# fabisp.net
KiCad netlist of a schematic drawn in EAGLE
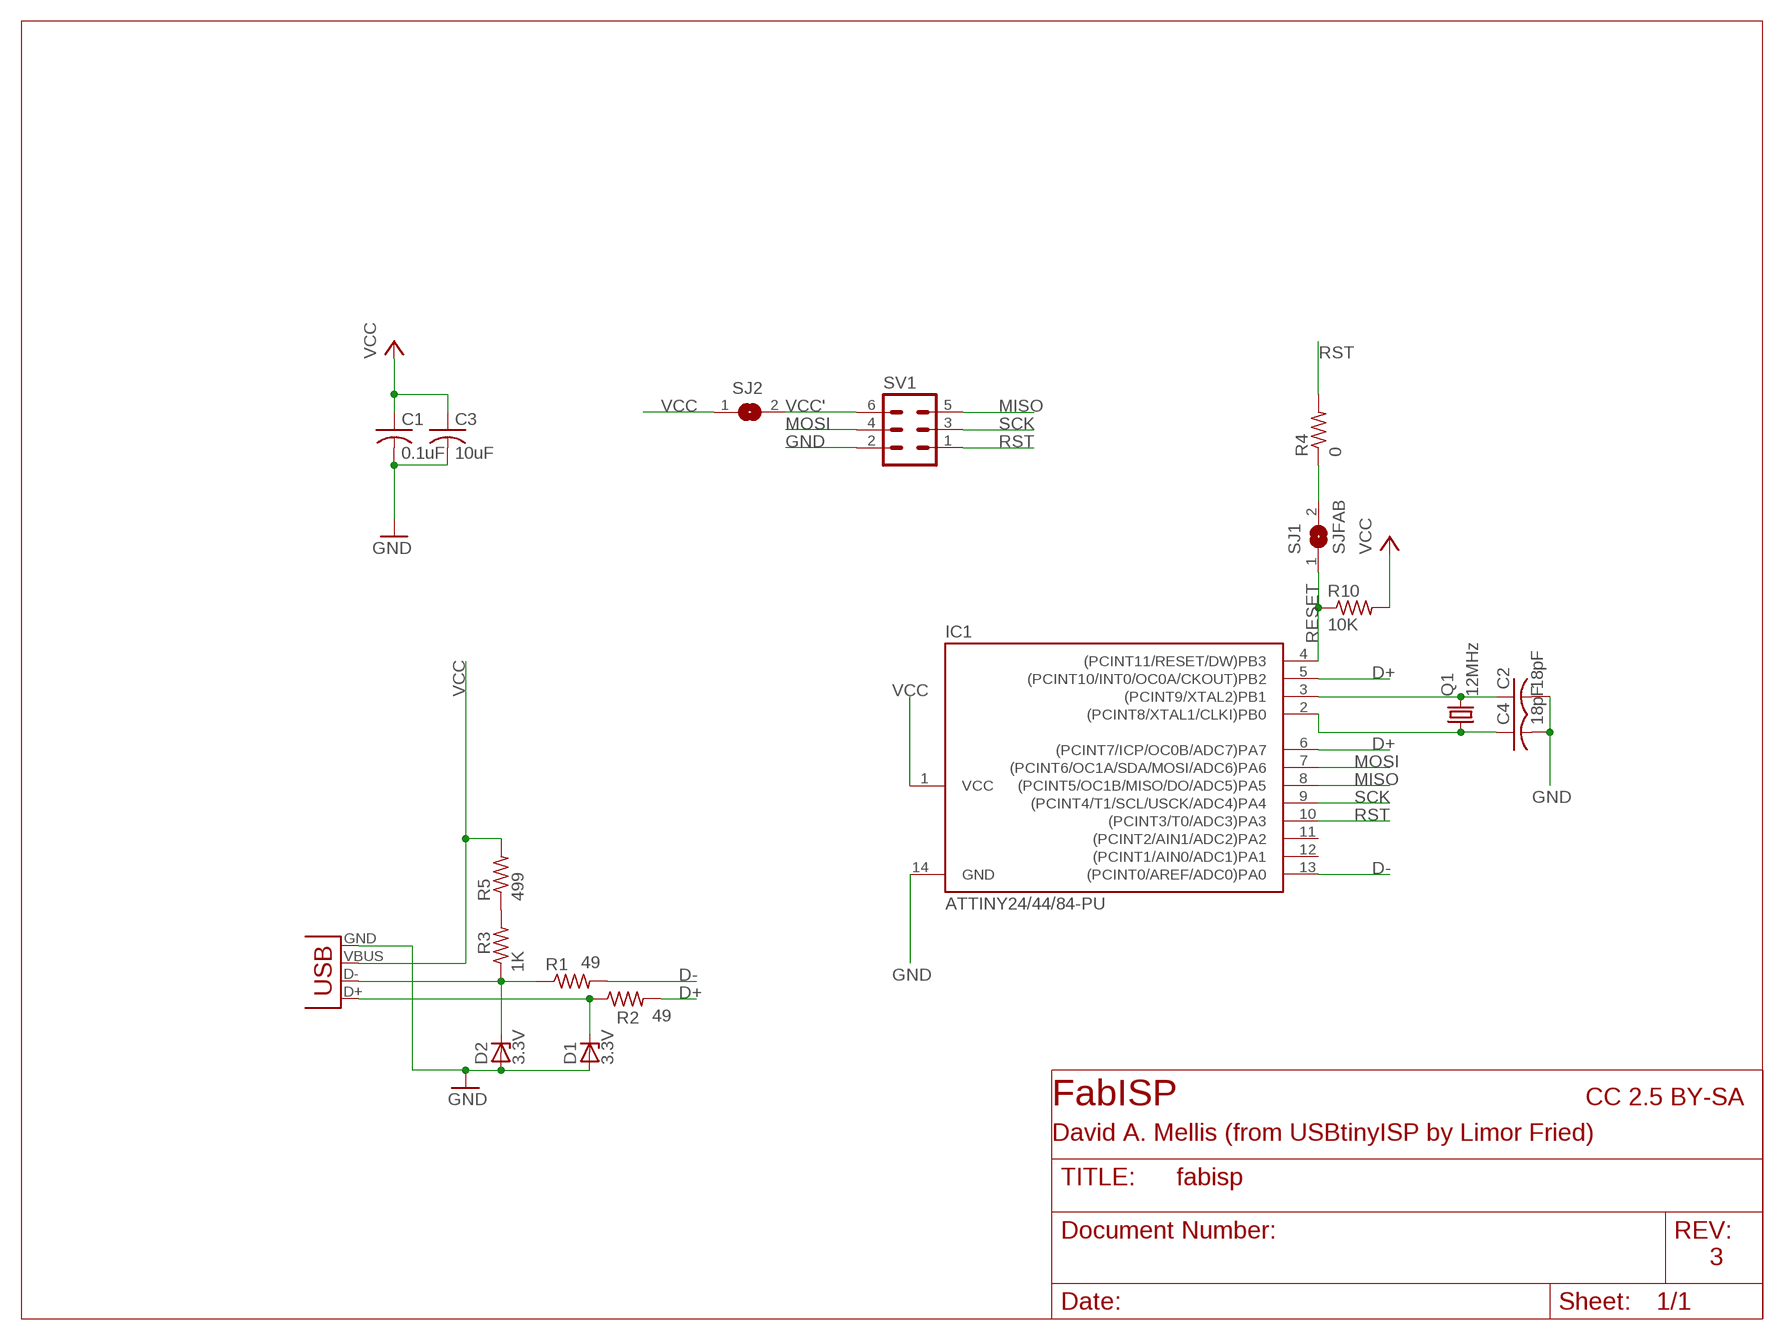
[diagram p0: schematic, sheet 1]

(export (version "E")
  (design (tool "Eeschema 10.0.6"))
  (components
    (comp (ref "C1")
      (value "0.1uF")
      (footprint "eagle-import:C025-024X044")
      (libsource (lib "eagle-import") (part "rcl-ez_C-US025-024X044"))
    )
    (comp (ref "C2")
      (value "18pF")
      (footprint "eagle-import:C025-024X044")
      (libsource (lib "eagle-import") (part "C-US025-024X044"))
    )
    (comp (ref "C3")
      (value "10uF")
      (footprint "eagle-import:C025-024X044")
      (libsource (lib "eagle-import") (part "C-US025-024X044"))
    )
    (comp (ref "C4")
      (value "18pF")
      (footprint "eagle-import:C025-024X044")
      (libsource (lib "eagle-import") (part "C-US025-024X044"))
    )
    (comp (ref "D1")
      (value "3.3V")
      (footprint "eagle-import:DO41Z10")
      (libsource (lib "eagle-import") (part "ZENER_DIODEDO41Z10"))
    )
    (comp (ref "D2")
      (value "3.3V")
      (footprint "eagle-import:DO41Z10")
      (libsource (lib "eagle-import") (part "ZENER_DIODEDO41Z10"))
    )
    (comp (ref "IC1")
      (value "ATTINY24/44/84-PU")
      (footprint "eagle-import:DIL14")
      (libsource (lib "eagle-import") (part "ATTINY24/44/84-PU"))
    )
    (comp (ref "Q1")
      (value "12MHz")
      (footprint "eagle-import:HC49U-V")
      (libsource (lib "eagle-import") (part "CRYSTALHC49U-V"))
    )
    (comp (ref "R1")
      (value "49")
      (footprint "eagle-import:0204_7")
      (libsource (lib "eagle-import") (part "rcl-ez_R-US_0204/7"))
    )
    (comp (ref "R2")
      (value "49")
      (footprint "eagle-import:0204_7")
      (libsource (lib "eagle-import") (part "rcl-ez_R-US_0204/7"))
    )
    (comp (ref "R3")
      (value "1K")
      (footprint "eagle-import:0204_7")
      (libsource (lib "eagle-import") (part "rcl-ez_R-US_0204/7"))
    )
    (comp (ref "R4")
      (value "0")
      (footprint "eagle-import:0204_7")
      (libsource (lib "eagle-import") (part "R-US_0204/7"))
    )
    (comp (ref "R5")
      (value "499")
      (footprint "eagle-import:0204_7")
      (libsource (lib "eagle-import") (part "R-US_0204/7"))
    )
    (comp (ref "R10")
      (value "10K")
      (footprint "eagle-import:0204_7")
      (libsource (lib "eagle-import") (part "rcl-ez_R-US_0204/7"))
    )
    (comp (ref "SJ1")
      (value "SJFAB")
      (footprint "eagle-import:SJFAB")
      (libsource (lib "eagle-import") (part "SJFAB"))
    )
    (comp (ref "SJ2")
      (value "SJFAB")
      (footprint "eagle-import:SJFAB")
      (libsource (lib "eagle-import") (part "SJFAB"))
    )
    (comp (ref "SV1")
      (value "MA03-2")
      (footprint "eagle-import:MA03-2")
      (libsource (lib "eagle-import") (part "MA03-2"))
    )
    (comp (ref "X1")
      (value "USB_MINIB")
      (footprint "eagle-import:USB_MINIB")
      (libsource (lib "eagle-import") (part "USB_MINIB"))
    )
  )
  (nets
    (net (code "1") (name "/D+") (class "Default")
      (node (ref "IC1") (pin "5") (pinfunction "(PCINT10/INT0/OC0A/CKOUT)PB2_5") (pintype "bidirectional"))
      (node (ref "IC1") (pin "6") (pinfunction "(PCINT7/ICP/OC0B/ADC7)PA7_6") (pintype "bidirectional"))
      (node (ref "R2") (pin "2") (pinfunction "2_2") (pintype "passive"))
    )
    (net (code "2") (name "/D-") (class "Default")
      (node (ref "IC1") (pin "13") (pinfunction "(PCINT0/AREF/ADC0)PA0_13") (pintype "bidirectional"))
      (node (ref "R1") (pin "2") (pinfunction "2_2") (pintype "passive"))
    )
    (net (code "3") (name "/MISO") (class "Default")
      (node (ref "IC1") (pin "8") (pinfunction "(PCINT5/OC1B/MISO/DO/ADC5)PA5_8") (pintype "bidirectional"))
      (node (ref "SV1") (pin "5") (pinfunction "5_5") (pintype "passive"))
    )
    (net (code "4") (name "/MOSI") (class "Default")
      (node (ref "IC1") (pin "7") (pinfunction "(PCINT6/OC1A/SDA/MOSI/ADC6)PA6_7") (pintype "bidirectional"))
      (node (ref "SV1") (pin "4") (pinfunction "4_4") (pintype "passive"))
    )
    (net (code "5") (name "/RESET") (class "Default")
      (node (ref "IC1") (pin "4") (pinfunction "(PCINT11/RESET/DW)PB3_4") (pintype "bidirectional"))
      (node (ref "R10") (pin "1") (pinfunction "1_1") (pintype "passive"))
      (node (ref "SJ1") (pin "1") (pinfunction "1_1") (pintype "passive"))
    )
    (net (code "6") (name "/RST") (class "Default")
      (node (ref "IC1") (pin "10") (pinfunction "(PCINT3/T0/ADC3)PA3_10") (pintype "bidirectional"))
      (node (ref "R4") (pin "2") (pinfunction "2_2") (pintype "passive"))
      (node (ref "SV1") (pin "1") (pinfunction "1_1") (pintype "passive"))
    )
    (net (code "7") (name "/SCK") (class "Default")
      (node (ref "IC1") (pin "9") (pinfunction "(PCINT4/T1/SCL/USCK/ADC4)PA4_9") (pintype "bidirectional"))
      (node (ref "SV1") (pin "3") (pinfunction "3_3") (pintype "passive"))
    )
    (net (code "8") (name "/VCC'") (class "Default")
      (node (ref "SJ2") (pin "2") (pinfunction "2_2") (pintype "passive"))
      (node (ref "SV1") (pin "6") (pinfunction "6_6") (pintype "passive"))
    )
    (net (code "9") (name "GND") (class "Default")
      (node (ref "C1") (pin "2") (pinfunction "2_2") (pintype "passive"))
      (node (ref "C2") (pin "2") (pinfunction "2_2") (pintype "passive"))
      (node (ref "C3") (pin "2") (pinfunction "2_2") (pintype "passive"))
      (node (ref "C4") (pin "2") (pinfunction "2_2") (pintype "passive"))
      (node (ref "D1") (pin "A") (pinfunction "ANODE_A") (pintype "passive"))
      (node (ref "D2") (pin "A") (pinfunction "ANODE_A") (pintype "passive"))
      (node (ref "IC1") (pin "14") (pinfunction "GND_14") (pintype "power_in"))
      (node (ref "SV1") (pin "2") (pinfunction "2_2") (pintype "passive"))
      (node (ref "X1") (pin "GND") (pinfunction "GND_GND") (pintype "bidirectional"))
    )
    (net (code "10") (name "Net-(D1-CATHODE)") (class "Default")
      (node (ref "D1") (pin "C") (pinfunction "CATHODE_C") (pintype "passive"))
      (node (ref "R2") (pin "1") (pinfunction "1_1") (pintype "passive"))
      (node (ref "X1") (pin "D+") (pinfunction "D+_D+") (pintype "bidirectional"))
    )
    (net (code "11") (name "Net-(D2-CATHODE)") (class "Default")
      (node (ref "D2") (pin "C") (pinfunction "CATHODE_C") (pintype "passive"))
      (node (ref "R1") (pin "1") (pinfunction "1_1") (pintype "passive"))
      (node (ref "R3") (pin "1") (pinfunction "1_1") (pintype "passive"))
      (node (ref "X1") (pin "D-") (pinfunction "D-_D-") (pintype "bidirectional"))
    )
    (net (code "12") (name "Net-(IC1-(PCINT8{slash}XTAL1{slash}CLKI)PB0)") (class "Default")
      (node (ref "C4") (pin "1") (pinfunction "1_1") (pintype "passive"))
      (node (ref "IC1") (pin "2") (pinfunction "(PCINT8/XTAL1/CLKI)PB0_2") (pintype "bidirectional"))
      (node (ref "Q1") (pin "1") (pinfunction "1_1") (pintype "passive"))
    )
    (net (code "13") (name "Net-(IC1-(PCINT9{slash}XTAL2)PB1)") (class "Default")
      (node (ref "C2") (pin "1") (pinfunction "1_1") (pintype "passive"))
      (node (ref "IC1") (pin "3") (pinfunction "(PCINT9/XTAL2)PB1_3") (pintype "bidirectional"))
      (node (ref "Q1") (pin "2") (pinfunction "2_2") (pintype "passive"))
    )
    (net (code "14") (name "Net-(R3-Pad2)") (class "Default")
      (node (ref "R3") (pin "2") (pinfunction "2_2") (pintype "passive"))
      (node (ref "R5") (pin "1") (pinfunction "1_1") (pintype "passive"))
    )
    (net (code "15") (name "Net-(R4-Pad1)") (class "Default")
      (node (ref "R4") (pin "1") (pinfunction "1_1") (pintype "passive"))
      (node (ref "SJ1") (pin "2") (pinfunction "2_2") (pintype "passive"))
    )
    (net (code "16") (name "VCC") (class "Default")
      (node (ref "C1") (pin "1") (pinfunction "1_1") (pintype "passive"))
      (node (ref "C3") (pin "1") (pinfunction "1_1") (pintype "passive"))
      (node (ref "IC1") (pin "1") (pinfunction "VCC_1") (pintype "power_in"))
      (node (ref "R10") (pin "2") (pinfunction "2_2") (pintype "passive"))
      (node (ref "R5") (pin "2") (pinfunction "2_2") (pintype "passive"))
      (node (ref "SJ2") (pin "1") (pinfunction "1_1") (pintype "passive"))
      (node (ref "X1") (pin "VBUS") (pinfunction "VBUS_VBUS") (pintype "bidirectional"))
    )
    (net (code "17") (name "unconnected-(IC1-(PCINT1{slash}AIN0{slash}ADC1)PA1-Pad12)") (class "Default")
      (node (ref "IC1") (pin "12") (pinfunction "(PCINT1/AIN0/ADC1)PA1_12") (pintype "bidirectional"))
    )
    (net (code "18") (name "unconnected-(IC1-(PCINT2{slash}AIN1{slash}ADC2)PA2-Pad11)") (class "Default")
      (node (ref "IC1") (pin "11") (pinfunction "(PCINT2/AIN1/ADC2)PA2_11") (pintype "bidirectional"))
    )
  )
)
